# controller_board.net
KiCad netlist of a schematic drawn in EAGLE
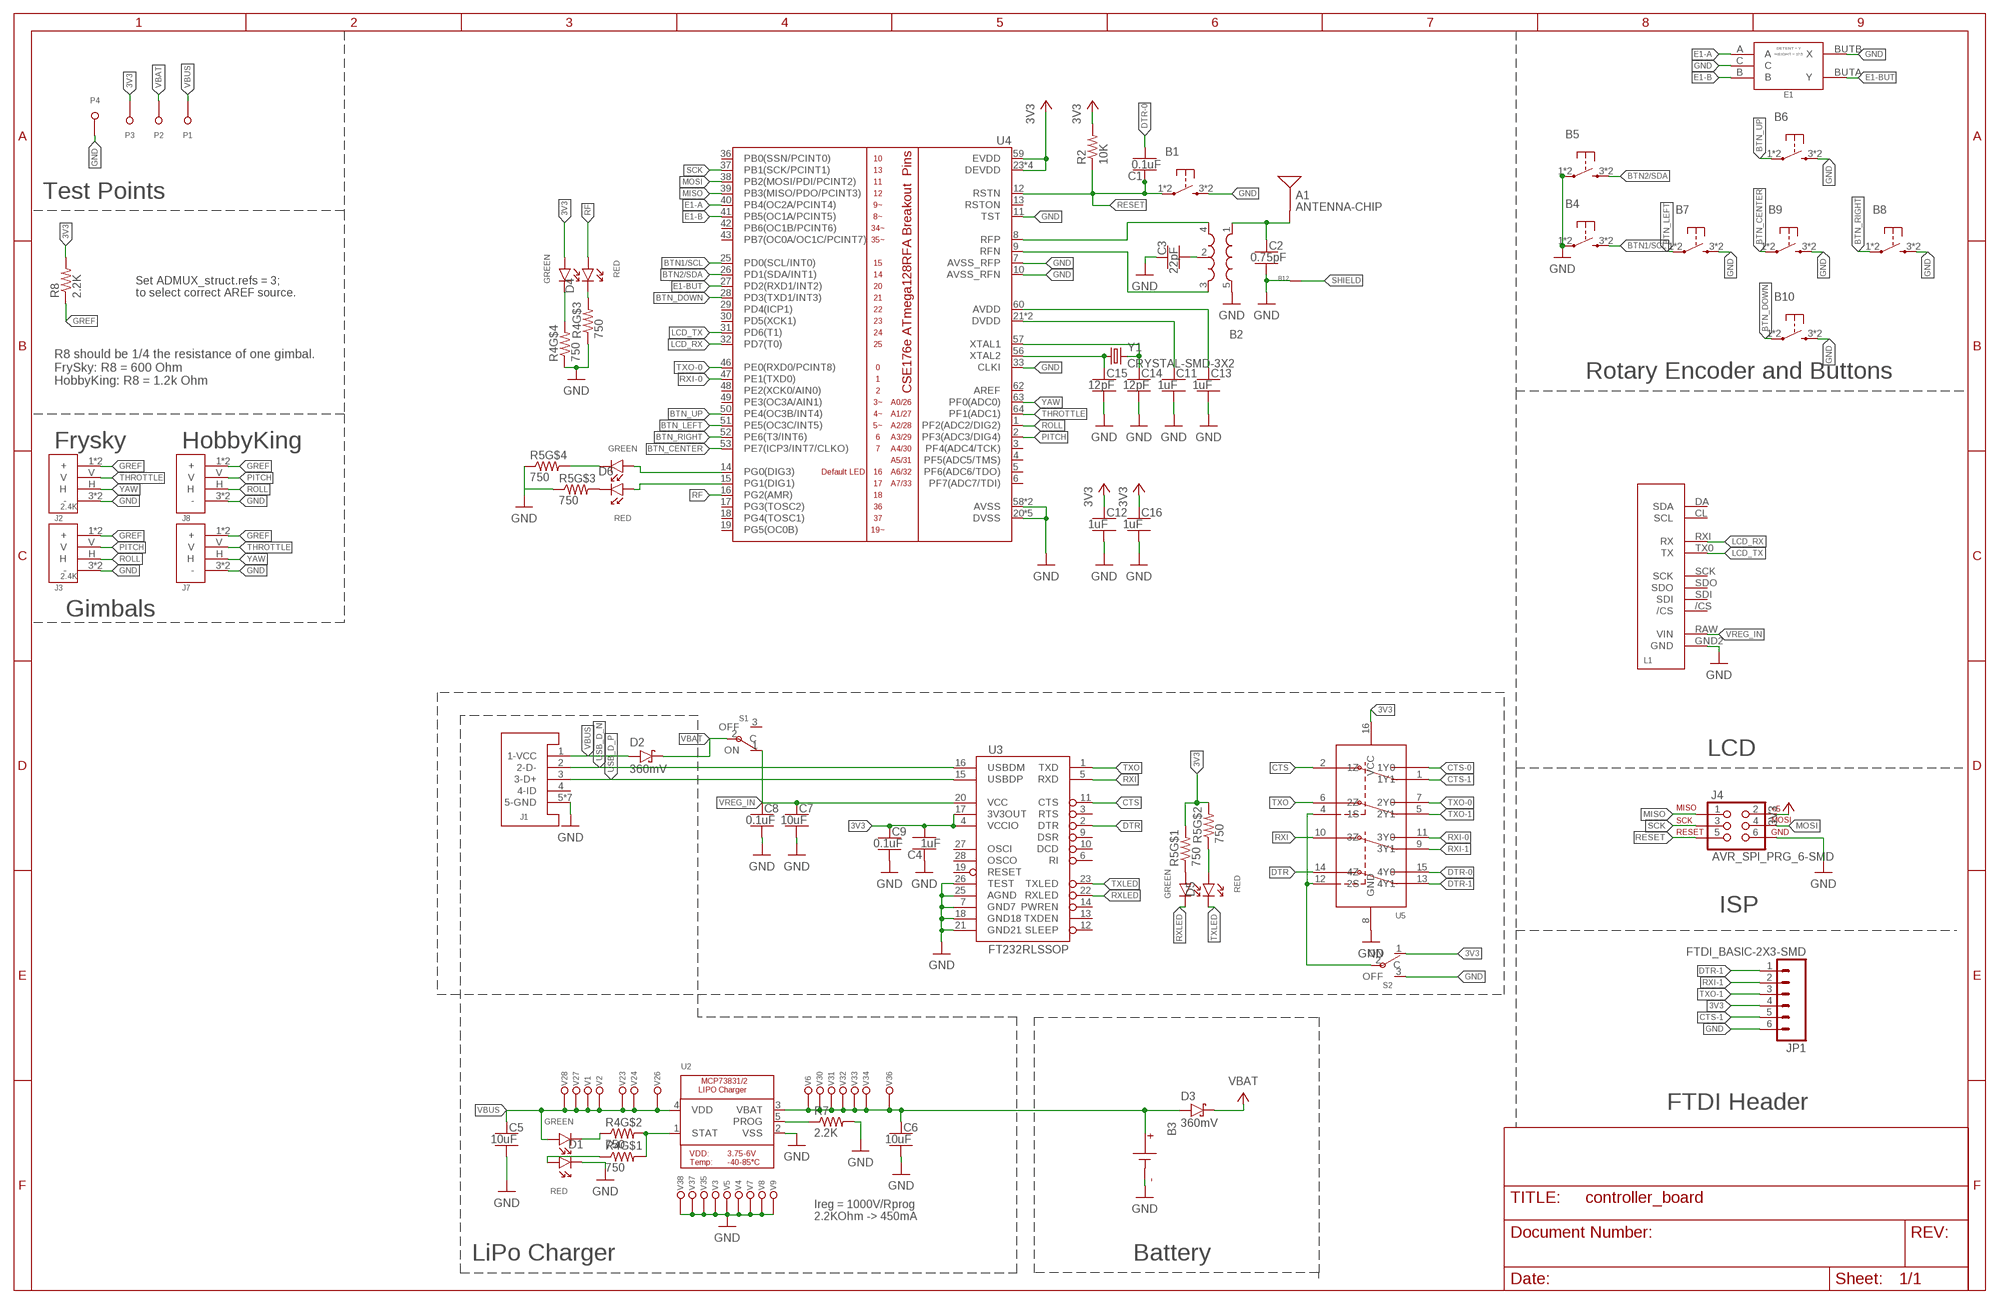
[diagram p0: schematic, sheet 1]

(export (version "E")
  (design (tool "Eeschema 10.0.6"))
  (components
    (comp (ref "A1")
      (value "ANTENNA-CHIP")
      (footprint "eagle-import:ANTENNA-CHIP")
      (fields
        (field (name "MFR") "Linx Technologies Inc.")
        (field (name "MPN") "ANT-2.45-CHP-T")
        (field (name "CREATOR") "Swanson")
        (field (name "REVIEWER") "Swanson")
      )
      (libsource (lib "eagle-import") (part "ANTENNA-CHIP"))
    )
    (comp (ref "B1")
      (value "PUSHBUTTON_-4.5X4.5")
      (footprint "eagle-import:4.5MM_TACTILE_SWITCH_TL3305AF160QG")
      (fields (field (name "CREATOR") "Swanson"))
      (libsource (lib "eagle-import") (part "PUSHBUTTON_-4.5X4.5"))
    )
    (comp (ref "B2")
      (value "BALUN0805")
      (footprint "eagle-import:BALUN")
      (fields
        (field (name "MFR") "Wurth Electronics Inc")
        (field (name "MPN") "748421245")
        (field (name "CREATOR") "Swanson")
        (field (name "REVIEWER") "Swanson")
      )
      (libsource (lib "eagle-import") (part "BALUN0805"))
    )
    (comp (ref "B3")
      (value "BATTERY-SMD")
      (footprint "eagle-import:MOLEX-BATTERY-CONNECTOR-SMD-51005-2P")
      (libsource (lib "eagle-import") (part "BATTERY-SMD"))
    )
    (comp (ref "B4")
      (value "PUSHBUTTON_-4.5X4.5")
      (footprint "eagle-import:4.5MM_TACTILE_SWITCH_TL3305AF160QG")
      (fields (field (name "CREATOR") "Swanson"))
      (libsource (lib "eagle-import") (part "PUSHBUTTON_-4.5X4.5"))
    )
    (comp (ref "B5")
      (value "PUSHBUTTON_-4.5X4.5")
      (footprint "eagle-import:4.5MM_TACTILE_SWITCH_TL3305AF160QG")
      (fields (field (name "CREATOR") "Swanson"))
      (libsource (lib "eagle-import") (part "PUSHBUTTON_-4.5X4.5"))
    )
    (comp (ref "B6")
      (value "PUSHBUTTON_-4.5X4.5")
      (footprint "eagle-import:4.5MM_TACTILE_SWITCH_TL3305AF160QG")
      (fields (field (name "CREATOR") "Swanson"))
      (libsource (lib "eagle-import") (part "PUSHBUTTON_-4.5X4.5"))
    )
    (comp (ref "B7")
      (value "PUSHBUTTON_-4.5X4.5")
      (footprint "eagle-import:4.5MM_TACTILE_SWITCH_TL3305AF160QG")
      (fields (field (name "CREATOR") "Swanson"))
      (libsource (lib "eagle-import") (part "PUSHBUTTON_-4.5X4.5"))
    )
    (comp (ref "B8")
      (value "PUSHBUTTON_-4.5X4.5")
      (footprint "eagle-import:4.5MM_TACTILE_SWITCH_TL3305AF160QG")
      (fields (field (name "CREATOR") "Swanson"))
      (libsource (lib "eagle-import") (part "PUSHBUTTON_-4.5X4.5"))
    )
    (comp (ref "B9")
      (value "PUSHBUTTON_-4.5X4.5")
      (footprint "eagle-import:4.5MM_TACTILE_SWITCH_TL3305AF160QG")
      (fields (field (name "CREATOR") "Swanson"))
      (libsource (lib "eagle-import") (part "PUSHBUTTON_-4.5X4.5"))
    )
    (comp (ref "B10")
      (value "PUSHBUTTON_-4.5X4.5")
      (footprint "eagle-import:4.5MM_TACTILE_SWITCH_TL3305AF160QG")
      (fields (field (name "CREATOR") "Swanson"))
      (libsource (lib "eagle-import") (part "PUSHBUTTON_-4.5X4.5"))
    )
    (comp (ref "B12")
      (value "NET_BRIDGE")
      (footprint "eagle-import:NET_BRIDGE")
      (fields (field (name "CREATOR") "Michael Gonzalez"))
      (libsource (lib "eagle-import") (part "NET_BRIDGE"))
    )
    (comp (ref "C1")
      (value "0.1uF")
      (footprint "eagle-import:CAPC1608X100")
      (fields (field (name "CREATOR") "Swanson"))
      (libsource (lib "eagle-import") (part "CAPACITOR-NP_SMD-0603_CERAMIC-0.1UF"))
    )
    (comp (ref "C2")
      (value "0.75pF")
      (footprint "eagle-import:CAPC1608X100")
      (fields (field (name "CREATOR") "Swanson"))
      (libsource (lib "eagle-import") (part "CAPACITOR-NP_SMD-0603_CERAMIC-0.75PF"))
    )
    (comp (ref "C3")
      (value "22pF")
      (footprint "eagle-import:CAPC1608X100")
      (fields (field (name "CREATOR") "Swanson"))
      (libsource (lib "eagle-import") (part "CAPACITOR-NP_SMD-0603_CERAMIC-22PF"))
    )
    (comp (ref "C4")
      (value "1uF")
      (footprint "eagle-import:CAPC1608X100")
      (fields (field (name "CREATOR") "Swanson"))
      (libsource (lib "eagle-import") (part "CAPACITOR-NP_SMD-0603_CERAMIC-1UF"))
    )
    (comp (ref "C5")
      (value "10uF")
      (footprint "eagle-import:CAPC1608X100")
      (fields (field (name "CREATOR") "Swanson"))
      (libsource (lib "eagle-import") (part "CAPACITOR-NP_SMD-0603_CERAMIC-10UF"))
    )
    (comp (ref "C6")
      (value "10uF")
      (footprint "eagle-import:CAPC1608X100")
      (fields (field (name "CREATOR") "Swanson"))
      (libsource (lib "eagle-import") (part "CAPACITOR-NP_SMD-0603_CERAMIC-10UF"))
    )
    (comp (ref "C7")
      (value "10uF")
      (footprint "eagle-import:CAPC1608X100")
      (fields (field (name "CREATOR") "Swanson"))
      (libsource (lib "eagle-import") (part "CAPACITOR-NP_SMD-0603_CERAMIC-10UF"))
    )
    (comp (ref "C8")
      (value "0.1uF")
      (footprint "eagle-import:CAPC1608X100")
      (fields (field (name "CREATOR") "Swanson"))
      (libsource (lib "eagle-import") (part "CAPACITOR-NP_SMD-0603_CERAMIC-0.1UF"))
    )
    (comp (ref "C9")
      (value "0.1uF")
      (footprint "eagle-import:CAPC1608X100")
      (fields (field (name "CREATOR") "Swanson"))
      (libsource (lib "eagle-import") (part "CAPACITOR-NP_SMD-0603_CERAMIC-0.1UF"))
    )
    (comp (ref "C11")
      (value "1uF")
      (footprint "eagle-import:CAPC1608X100")
      (fields (field (name "CREATOR") "Swanson"))
      (libsource (lib "eagle-import") (part "CAPACITOR-NP_SMD-0603_CERAMIC-1UF"))
    )
    (comp (ref "C12")
      (value "1uF")
      (footprint "eagle-import:CAPC1608X100")
      (fields (field (name "CREATOR") "Swanson"))
      (libsource (lib "eagle-import") (part "CAPACITOR-NP_SMD-0603_CERAMIC-1UF"))
    )
    (comp (ref "C13")
      (value "1uF")
      (footprint "eagle-import:CAPC1608X100")
      (fields (field (name "CREATOR") "Swanson"))
      (libsource (lib "eagle-import") (part "CAPACITOR-NP_SMD-0603_CERAMIC-1UF"))
    )
    (comp (ref "C14")
      (value "12pF")
      (footprint "eagle-import:CAPC1608X100")
      (fields (field (name "CREATOR") "Swanson"))
      (libsource (lib "eagle-import") (part "CAPACITOR-NP_SMD-0603_CERAMIC-12PF"))
    )
    (comp (ref "C15")
      (value "12pF")
      (footprint "eagle-import:CAPC1608X100")
      (fields (field (name "CREATOR") "Swanson"))
      (libsource (lib "eagle-import") (part "CAPACITOR-NP_SMD-0603_CERAMIC-12PF"))
    )
    (comp (ref "C16")
      (value "1uF")
      (footprint "eagle-import:CAPC1608X100")
      (fields (field (name "CREATOR") "Swanson"))
      (libsource (lib "eagle-import") (part "CAPACITOR-NP_SMD-0603_CERAMIC-1UF"))
    )
    (comp (ref "D1")
      (value "LED-2X-GREEN/RED-1.6X1.5MM")
      (footprint "eagle-import:LED-2X-LITE-ON-1.6MMX1.5MM")
      (fields
        (field (name "COLOR2") "RED")
        (field (name "COLOR1") "GREEN")
        (field (name "CREATOR") "Swanson")
      )
      (libsource (lib "eagle-import") (part "LED-2X-GREEN/RED-1.6X1.5MM"))
    )
    (comp (ref "D2")
      (value "360mV")
      (footprint "eagle-import:SOD3716X135_HS")
      (fields
        (field (name "MFR") "Toshiba Semiconductor and Storage")
        (field (name "MPN") "CRS08(TE85L,Q,M)")
        (field (name "CREATOR") "Swanson")
        (field (name "REVIEWER") "Swanson")
      )
      (libsource (lib "eagle-import") (part "DIODE-SCHOTTKY_SMD-SOD123-360MV"))
    )
    (comp (ref "D3")
      (value "360mV")
      (footprint "eagle-import:SOD3716X135_HS")
      (fields
        (field (name "MFR") "Toshiba Semiconductor and Storage")
        (field (name "MPN") "CRS08(TE85L,Q,M)")
        (field (name "CREATOR") "Swanson")
        (field (name "REVIEWER") "Swanson")
      )
      (libsource (lib "eagle-import") (part "DIODE-SCHOTTKY_SMD-SOD123-360MV"))
    )
    (comp (ref "D4")
      (value "LED-2X-GREEN/RED-1.6X1.5MM")
      (footprint "eagle-import:LED-2X-LITE-ON-1.6MMX1.5MM")
      (fields
        (field (name "COLOR2") "RED")
        (field (name "COLOR1") "GREEN")
        (field (name "CREATOR") "Swanson")
      )
      (libsource (lib "eagle-import") (part "LED-2X-GREEN/RED-1.6X1.5MM"))
    )
    (comp (ref "D5")
      (value "LED-2X-GREEN/RED-1.6X1.5MM")
      (footprint "eagle-import:LED-2X-LITE-ON-1.6MMX1.5MM")
      (fields
        (field (name "COLOR2") "RED")
        (field (name "COLOR1") "GREEN")
        (field (name "CREATOR") "Swanson")
      )
      (libsource (lib "eagle-import") (part "LED-2X-GREEN/RED-1.6X1.5MM"))
    )
    (comp (ref "D6")
      (value "LED-2X-GREEN/RED-1.6X1.5MM")
      (footprint "eagle-import:LED-2X-LITE-ON-1.6MMX1.5MM")
      (fields
        (field (name "COLOR2") "RED")
        (field (name "COLOR1") "GREEN")
        (field (name "CREATOR") "Swanson")
      )
      (libsource (lib "eagle-import") (part "LED-2X-GREEN/RED-1.6X1.5MM"))
    )
    (comp (ref "E1")
      (value "ROTARY-ENCODER-W/BUTTON-BOURNS-PEC12R-4217F")
      (footprint "eagle-import:BOURNS-PEC12R")
      (fields (field (name "DETENT") "Y") (field (name "HEIGHT") "17.5") (field (name "CREATOR") "Swanson"))
      (libsource (lib "eagle-import") (part "ROTARY-ENCODER-W/BUTTON-BOURNS-PEC12R-4217F"))
    )
    (comp (ref "J1")
      (value "USB-MICROA-AMPHENOL-10118192-0001LF")
      (footprint "eagle-import:USB-MICROA-10118192-0001LF")
      (fields (field (name "CREATOR") "Swanson"))
      (libsource (lib "eagle-import") (part "USB-MICROA-AMPHENOL-10118192-0001LF"))
    )
    (comp (ref "J2")
      (value "2.4K")
      (footprint "eagle-import:JST-13-PTH")
      (fields (field (name "CREATOR") "Swanson"))
      (libsource (lib "eagle-import") (part "FRSKY-GIMBAL-FRYSKY"))
    )
    (comp (ref "J3")
      (value "2.4K")
      (footprint "eagle-import:JST-13-PTH")
      (fields (field (name "SPICEPREFIX") "E") (field (name "CREATOR") "Swanson"))
      (libsource (lib "eagle-import") (part "FRSKY-GIMBAL-FRYSKY"))
    )
    (comp (ref "J4")
      (value "AVR_SPI_PRG_6-SMD")
      (footprint "eagle-import:2X3-SMD")
      (fields (field (name "CREATOR") "Swanson"))
      (libsource (lib "eagle-import") (part "AVR_SPI_PRG_6-SMD"))
    )
    (comp (ref "J7")
      (value "FRSKY-GIMBAL-2X-SERVO-SMD")
      (footprint "eagle-import:2X-SERVO-SMD")
      (libsource (lib "eagle-import") (part "FRSKY-GIMBAL-2X-SERVO-SMD"))
    )
    (comp (ref "J8")
      (value "FRSKY-GIMBAL-2X-SERVO-SMD")
      (footprint "eagle-import:2X-SERVO-SMD")
      (libsource (lib "eagle-import") (part "FRSKY-GIMBAL-2X-SERVO-SMD"))
    )
    (comp (ref "JP1")
      (value "FTDI_BASIC-2X3-SMD")
      (footprint "eagle-import:FTDI-2X3-SMD")
      (fields (field (name "CREATOR") "Swanson"))
      (libsource (lib "eagle-import") (part "FTDI_BASIC-2X3-SMD"))
    )
    (comp (ref "L1")
      (value "SPARKFUN_SERLCD_SERIAL_REDUCED-SMD")
      (footprint "eagle-import:SPARKFUN_SERLCD_16X2_REDUCED_SMD")
      (fields (field (name "CREATOR") "Swanson"))
      (libsource (lib "eagle-import") (part "SPARKFUN_SERLCD_SERIAL_REDUCED-SMD"))
    )
    (comp (ref "P1")
      (value "TEST-POINT")
      (footprint "eagle-import:TEST-POINT-KEYSTONE-5000")
      (fields (field (name "CREATOR") "Swanson"))
      (libsource (lib "eagle-import") (part "TEST-POINT"))
    )
    (comp (ref "P2")
      (value "TEST-POINT")
      (footprint "eagle-import:TEST-POINT-KEYSTONE-5000")
      (fields (field (name "CREATOR") "Swanson"))
      (libsource (lib "eagle-import") (part "TEST-POINT"))
    )
    (comp (ref "P3")
      (value "TEST-POINT")
      (footprint "eagle-import:TEST-POINT-KEYSTONE-5000")
      (fields (field (name "CREATOR") "Swanson"))
      (libsource (lib "eagle-import") (part "TEST-POINT"))
    )
    (comp (ref "P4")
      (value "TEST-POINT")
      (footprint "eagle-import:TEST-POINT-KEYSTONE-5000")
      (fields (field (name "CREATOR") "Swanson"))
      (libsource (lib "eagle-import") (part "TEST-POINT"))
    )
    (comp (ref "R2")
      (value "10K")
      (footprint "eagle-import:RESC1608X55")
      (fields (field (name "CREATOR") "Swanson"))
      (libsource (lib "eagle-import") (part "RESISTOR_SMD-0603-10K"))
    )
    (comp (ref "R4")
      (value "750")
      (footprint "eagle-import:RESCAXS50P200X100X45-8")
      (fields (field (name "CREATOR") "Swanson"))
      (libsource (lib "eagle-import") (part "RESISTOR-PACK-4X-750"))
    )
    (comp (ref "R5")
      (value "750")
      (footprint "eagle-import:RESCAXS50P200X100X45-8")
      (fields (field (name "CREATOR") "Swanson"))
      (libsource (lib "eagle-import") (part "RESISTOR-PACK-4X-750"))
    )
    (comp (ref "R7")
      (value "2.2K")
      (footprint "eagle-import:RESC1608X55")
      (fields (field (name "CREATOR") "Swanson"))
      (libsource (lib "eagle-import") (part "RESISTOR_SMD-0603-2.2K"))
    )
    (comp (ref "R8")
      (value "2.2K")
      (footprint "eagle-import:RESC1608X55")
      (fields (field (name "CREATOR") "Swanson"))
      (libsource (lib "eagle-import") (part "RESISTOR_SMD-0603-2.2K"))
    )
    (comp (ref "S1")
      (value "POWER-SWITCH-MFS201N-9-Z-SMD-VERTICAL")
      (footprint "eagle-import:JS102011JCQN")
      (fields (field (name "CREATOR") "Swanson"))
      (libsource (lib "eagle-import") (part "POWER-SWITCH-MFS201N-9-Z-SMD-VERTICAL"))
    )
    (comp (ref "S2")
      (value "POWER-SWITCH-MFS201N-9-Z-SMD-VERTICAL")
      (footprint "eagle-import:JS102011JCQN")
      (fields (field (name "CREATOR") "Swanson"))
      (libsource (lib "eagle-import") (part "POWER-SWITCH-MFS201N-9-Z-SMD-VERTICAL"))
    )
    (comp (ref "U2")
      (value "MCP73831T-2ACI/OT")
      (footprint "eagle-import:SOT23-5")
      (fields (field (name "CREATOR") "Adafruit"))
      (libsource (lib "eagle-import") (part "MCP73831/2"))
    )
    (comp (ref "U3")
      (value "FT232RLSSOP")
      (footprint "eagle-import:SSOP28DB")
      (fields (field (name "CREATOR") "Swanson"))
      (libsource (lib "eagle-import") (part "FT232RLSSOP"))
    )
    (comp (ref "U4")
      (value "ATMEGA128RFA1")
      (footprint "eagle-import:QFN-64")
      (fields
        (field (name "MFR") "Atmel")
        (field (name "MPN") "ATMEGA128RFA1-ZUR00")
        (field (name "CREATOR") "Swanson")
        (field (name "REVIEWER") "Swanson")
      )
      (libsource (lib "eagle-import") (part "ATMEGA128RFA1"))
    )
    (comp (ref "U5")
      (value "DPDT-X2")
      (footprint "eagle-import:SOP65P640X110-16")
      (fields (field (name "CREATOR") "Swanson"))
      (libsource (lib "eagle-import") (part "DPDT-X2"))
    )
    (comp (ref "V1")
      (value "LOCKED-VIA-0.2")
      (footprint "eagle-import:VIA-0.2MM")
      (fields (field (name "CREATOR") "Swanson"))
      (libsource (lib "eagle-import") (part "LOCKED-VIA-0.2"))
    )
    (comp (ref "V2")
      (value "LOCKED-VIA-0.2")
      (footprint "eagle-import:VIA-0.2MM")
      (fields (field (name "CREATOR") "Swanson"))
      (libsource (lib "eagle-import") (part "LOCKED-VIA-0.2"))
    )
    (comp (ref "V3")
      (value "LOCKED-VIA-0.2")
      (footprint "eagle-import:VIA-0.2MM")
      (fields (field (name "CREATOR") "Swanson"))
      (libsource (lib "eagle-import") (part "LOCKED-VIA-0.2"))
    )
    (comp (ref "V4")
      (value "LOCKED-VIA-0.2")
      (footprint "eagle-import:VIA-0.2MM")
      (fields (field (name "CREATOR") "Swanson"))
      (libsource (lib "eagle-import") (part "LOCKED-VIA-0.2"))
    )
    (comp (ref "V5")
      (value "LOCKED-VIA-0.2")
      (footprint "eagle-import:VIA-0.2MM")
      (fields (field (name "CREATOR") "Swanson"))
      (libsource (lib "eagle-import") (part "LOCKED-VIA-0.2"))
    )
    (comp (ref "V6")
      (value "LOCKED-VIA-0.2")
      (footprint "eagle-import:VIA-0.2MM")
      (fields (field (name "CREATOR") "Swanson"))
      (libsource (lib "eagle-import") (part "LOCKED-VIA-0.2"))
    )
    (comp (ref "V7")
      (value "LOCKED-VIA-0.2")
      (footprint "eagle-import:VIA-0.2MM")
      (fields (field (name "CREATOR") "Swanson"))
      (libsource (lib "eagle-import") (part "LOCKED-VIA-0.2"))
    )
    (comp (ref "V8")
      (value "LOCKED-VIA-0.2")
      (footprint "eagle-import:VIA-0.2MM")
      (fields (field (name "CREATOR") "Swanson"))
      (libsource (lib "eagle-import") (part "LOCKED-VIA-0.2"))
    )
    (comp (ref "V9")
      (value "LOCKED-VIA-0.2")
      (footprint "eagle-import:VIA-0.2MM")
      (fields (field (name "CREATOR") "Swanson"))
      (libsource (lib "eagle-import") (part "LOCKED-VIA-0.2"))
    )
    (comp (ref "V23")
      (value "LOCKED-VIA-0.2")
      (footprint "eagle-import:VIA-0.2MM")
      (fields (field (name "CREATOR") "Swanson"))
      (libsource (lib "eagle-import") (part "LOCKED-VIA-0.2"))
    )
    (comp (ref "V24")
      (value "LOCKED-VIA-0.2")
      (footprint "eagle-import:VIA-0.2MM")
      (fields (field (name "CREATOR") "Swanson"))
      (libsource (lib "eagle-import") (part "LOCKED-VIA-0.2"))
    )
    (comp (ref "V26")
      (value "LOCKED-VIA-0.2")
      (footprint "eagle-import:VIA-0.2MM")
      (fields (field (name "CREATOR") "Swanson"))
      (libsource (lib "eagle-import") (part "LOCKED-VIA-0.2"))
    )
    (comp (ref "V27")
      (value "LOCKED-VIA-0.2")
      (footprint "eagle-import:VIA-0.2MM")
      (fields (field (name "CREATOR") "Swanson"))
      (libsource (lib "eagle-import") (part "LOCKED-VIA-0.2"))
    )
    (comp (ref "V28")
      (value "LOCKED-VIA-0.2")
      (footprint "eagle-import:VIA-0.2MM")
      (fields (field (name "CREATOR") "Swanson"))
      (libsource (lib "eagle-import") (part "LOCKED-VIA-0.2"))
    )
    (comp (ref "V30")
      (value "LOCKED-VIA-0.2")
      (footprint "eagle-import:VIA-0.2MM")
      (fields (field (name "CREATOR") "Swanson"))
      (libsource (lib "eagle-import") (part "LOCKED-VIA-0.2"))
    )
    (comp (ref "V31")
      (value "LOCKED-VIA-0.2")
      (footprint "eagle-import:VIA-0.2MM")
      (fields (field (name "CREATOR") "Swanson"))
      (libsource (lib "eagle-import") (part "LOCKED-VIA-0.2"))
    )
    (comp (ref "V32")
      (value "LOCKED-VIA-0.2")
      (footprint "eagle-import:VIA-0.2MM")
      (fields (field (name "CREATOR") "Swanson"))
      (libsource (lib "eagle-import") (part "LOCKED-VIA-0.2"))
    )
    (comp (ref "V33")
      (value "LOCKED-VIA-0.2")
      (footprint "eagle-import:VIA-0.2MM")
      (fields (field (name "CREATOR") "Swanson"))
      (libsource (lib "eagle-import") (part "LOCKED-VIA-0.2"))
    )
    (comp (ref "V34")
      (value "LOCKED-VIA-0.2")
      (footprint "eagle-import:VIA-0.2MM")
      (fields (field (name "CREATOR") "Swanson"))
      (libsource (lib "eagle-import") (part "LOCKED-VIA-0.2"))
    )
    (comp (ref "V35")
      (value "LOCKED-VIA-0.2")
      (footprint "eagle-import:VIA-0.2MM")
      (fields (field (name "CREATOR") "Swanson"))
      (libsource (lib "eagle-import") (part "LOCKED-VIA-0.2"))
    )
    (comp (ref "V36")
      (value "LOCKED-VIA-0.2")
      (footprint "eagle-import:VIA-0.2MM")
      (fields (field (name "CREATOR") "Swanson"))
      (libsource (lib "eagle-import") (part "LOCKED-VIA-0.2"))
    )
    (comp (ref "V37")
      (value "LOCKED-VIA-0.2")
      (footprint "eagle-import:VIA-0.2MM")
      (fields (field (name "CREATOR") "Swanson"))
      (libsource (lib "eagle-import") (part "LOCKED-VIA-0.2"))
    )
    (comp (ref "V38")
      (value "LOCKED-VIA-0.2")
      (footprint "eagle-import:VIA-0.2MM")
      (fields (field (name "CREATOR") "Swanson"))
      (libsource (lib "eagle-import") (part "LOCKED-VIA-0.2"))
    )
    (comp (ref "Y1")
      (value "CRYSTAL-SMD-3X2")
      (footprint "eagle-import:OSCCC320X250X85")
      (fields (field (name "CREATOR") "Swanson"))
      (libsource (lib "eagle-import") (part "CRYSTAL-SMD-3X2"))
    )
  )
  (nets
    (net (code "1") (name "3V3") (class "Default")
      (node (ref "C12") (pin "1") (pinfunction "1_1") (pintype "passive"))
      (node (ref "C16") (pin "1") (pinfunction "1_1") (pintype "passive"))
      (node (ref "C4") (pin "2") (pinfunction "2_2") (pintype "passive"))
      (node (ref "C9") (pin "1") (pinfunction "1_1") (pintype "passive"))
      (node (ref "D4") (pin "A2") (pinfunction "A2_A2") (pintype "passive"))
      (node (ref "J4") (pin "2") (pinfunction "2_2") (pintype "passive"))
      (node (ref "JP1") (pin "4") (pinfunction "4_4") (pintype "passive"))
      (node (ref "P3") (pin "T") (pinfunction "T_T") (pintype "bidirectional"))
      (node (ref "R2") (pin "2") (pinfunction "2_2") (pintype "passive"))
      (node (ref "R5") (pin "5") (pinfunction "2_5") (pintype "passive"))
      (node (ref "R5") (pin "6") (pinfunction "2_6") (pintype "passive"))
      (node (ref "R8") (pin "2") (pinfunction "2_2") (pintype "passive"))
      (node (ref "S2") (pin "1") (pinfunction "ON_1") (pintype "bidirectional"))
      (node (ref "U3") (pin "17") (pinfunction "3V3OUT_17") (pintype "output"))
      (node (ref "U3") (pin "4") (pinfunction "VCCIO_4") (pintype "power_in"))
      (node (ref "U4") (pin "23") (pinfunction "DEVDD_23") (pintype "bidirectional"))
      (node (ref "U4") (pin "34") (pinfunction "DEVDD_34") (pintype "bidirectional"))
      (node (ref "U4") (pin "44") (pinfunction "DEVDD_44") (pintype "bidirectional"))
      (node (ref "U4") (pin "54") (pinfunction "DEVDD_54") (pintype "bidirectional"))
      (node (ref "U4") (pin "59") (pinfunction "EVDD_59") (pintype "bidirectional"))
      (node (ref "U5") (pin "16") (pinfunction "VCC_16") (pintype "bidirectional"))
    )
    (net (code "2") (name "BTN1{slash}SCL") (class "Default")
      (node (ref "B4") (pin "3") (pinfunction "2_3") (pintype "passive"))
      (node (ref "B4") (pin "4") (pinfunction "2_4") (pintype "passive"))
      (node (ref "U4") (pin "25") (pinfunction "PD0(SCL/INT0)_25") (pintype "bidirectional"))
    )
    (net (code "3") (name "BTN2{slash}SDA") (class "Default")
      (node (ref "B5") (pin "3") (pinfunction "2_3") (pintype "passive"))
      (node (ref "B5") (pin "4") (pinfunction "2_4") (pintype "passive"))
      (node (ref "U4") (pin "26") (pinfunction "PD1(SDA/INT1)_26") (pintype "bidirectional"))
    )
    (net (code "4") (name "BTN_CENTER") (class "Default")
      (node (ref "B9") (pin "1") (pinfunction "1_1") (pintype "passive"))
      (node (ref "B9") (pin "2") (pinfunction "1_2") (pintype "passive"))
      (node (ref "U4") (pin "53") (pinfunction "PE7(ICP3/INT7/CLKO)_53") (pintype "bidirectional"))
    )
    (net (code "5") (name "BTN_DOWN") (class "Default")
      (node (ref "B10") (pin "1") (pinfunction "1_1") (pintype "passive"))
      (node (ref "B10") (pin "2") (pinfunction "1_2") (pintype "passive"))
      (node (ref "U4") (pin "28") (pinfunction "PD3(TXD1/INT3)_28") (pintype "bidirectional"))
    )
    (net (code "6") (name "BTN_LEFT") (class "Default")
      (node (ref "B7") (pin "1") (pinfunction "1_1") (pintype "passive"))
      (node (ref "B7") (pin "2") (pinfunction "1_2") (pintype "passive"))
      (node (ref "U4") (pin "51") (pinfunction "PE5(OC3C/INT5)_51") (pintype "bidirectional"))
    )
    (net (code "7") (name "BTN_RIGHT") (class "Default")
      (node (ref "B8") (pin "1") (pinfunction "1_1") (pintype "passive"))
      (node (ref "B8") (pin "2") (pinfunction "1_2") (pintype "passive"))
      (node (ref "U4") (pin "52") (pinfunction "PE6(T3/INT6)_52") (pintype "bidirectional"))
    )
    (net (code "8") (name "BTN_UP") (class "Default")
      (node (ref "B6") (pin "1") (pinfunction "1_1") (pintype "passive"))
      (node (ref "B6") (pin "2") (pinfunction "1_2") (pintype "passive"))
      (node (ref "U4") (pin "50") (pinfunction "PE4(OC3B/INT4)_50") (pintype "bidirectional"))
    )
    (net (code "9") (name "CTS") (class "Default")
      (node (ref "U3") (pin "11") (pinfunction "CTS_11") (pintype "input"))
      (node (ref "U5") (pin "2") (pinfunction "1Z_2") (pintype "bidirectional"))
    )
    (net (code "10") (name "CTS-0") (class "Default")
      (node (ref "U5") (pin "3") (pinfunction "1Y0_3") (pintype "bidirectional"))
    )
    (net (code "11") (name "CTS-1") (class "Default")
      (node (ref "JP1") (pin "5") (pinfunction "5_5") (pintype "passive"))
      (node (ref "U5") (pin "1") (pinfunction "1Y1_1") (pintype "bidirectional"))
    )
    (net (code "12") (name "DTR") (class "Default")
      (node (ref "U3") (pin "2") (pinfunction "DTR_2") (pintype "output"))
      (node (ref "U5") (pin "14") (pinfunction "4Z_14") (pintype "bidirectional"))
    )
    (net (code "13") (name "DTR-0") (class "Default")
      (node (ref "C1") (pin "2") (pinfunction "2_2") (pintype "passive"))
      (node (ref "U5") (pin "15") (pinfunction "4Y0_15") (pintype "bidirectional"))
    )
    (net (code "14") (name "DTR-1") (class "Default")
      (node (ref "JP1") (pin "1") (pinfunction "1_1") (pintype "passive"))
      (node (ref "U5") (pin "13") (pinfunction "4Y1_13") (pintype "bidirectional"))
    )
    (net (code "15") (name "E1-A") (class "Default")
      (node (ref "E1") (pin "A") (pinfunction "A_A") (pintype "bidirectional"))
      (node (ref "U4") (pin "40") (pinfunction "PB4(OC2A/PCINT4)_40") (pintype "bidirectional"))
    )
    (net (code "16") (name "E1-B") (class "Default")
      (node (ref "E1") (pin "B") (pinfunction "B_B") (pintype "bidirectional"))
      (node (ref "U4") (pin "41") (pinfunction "PB5(OC1A/PCINT5)_41") (pintype "bidirectional"))
    )
    (net (code "17") (name "E1-BUT") (class "Default")
      (node (ref "E1") (pin "BUTA") (pinfunction "Y_BUTA") (pintype "bidirectional"))
      (node (ref "U4") (pin "27") (pinfunction "PD2(RXD1/INT2)_27") (pintype "bidirectional"))
    )
    (net (code "18") (name "GND") (class "Default")
      (node (ref "B1") (pin "3") (pinfunction "2_3") (pintype "passive"))
      (node (ref "B1") (pin "4") (pinfunction "2_4") (pintype "passive"))
      (node (ref "B10") (pin "3") (pinfunction "2_3") (pintype "passive"))
      (node (ref "B10") (pin "4") (pinfunction "2_4") (pintype "passive"))
      (node (ref "B12") (pin "P1") (pinfunction "P1_P1") (pintype "bidirectional"))
      (node (ref "B2") (pin "5") (pinfunction "GND_5") (pintype "bidirectional"))
      (node (ref "B3") (pin "G") (pinfunction "N_G") (pintype "bidirectional"))
      (node (ref "B3") (pin "G2") (pinfunction "N_G2") (pintype "bidirectional"))
      (node (ref "B3") (pin "G3") (pinfunction "N_G3") (pintype "bidirectional"))
      (node (ref "B4") (pin "1") (pinfunction "1_1") (pintype "passive"))
      (node (ref "B4") (pin "2") (pinfunction "1_2") (pintype "passive"))
      (node (ref "B5") (pin "1") (pinfunction "1_1") (pintype "passive"))
      (node (ref "B5") (pin "2") (pinfunction "1_2") (pintype "passive"))
      (node (ref "B6") (pin "3") (pinfunction "2_3") (pintype "passive"))
      (node (ref "B6") (pin "4") (pinfunction "2_4") (pintype "passive"))
      (node (ref "B7") (pin "3") (pinfunction "2_3") (pintype "passive"))
      (node (ref "B7") (pin "4") (pinfunction "2_4") (pintype "passive"))
      (node (ref "B8") (pin "3") (pinfunction "2_3") (pintype "passive"))
      (node (ref "B8") (pin "4") (pinfunction "2_4") (pintype "passive"))
      (node (ref "B9") (pin "3") (pinfunction "2_3") (pintype "passive"))
      (node (ref "B9") (pin "4") (pinfunction "2_4") (pintype "passive"))
      (node (ref "C11") (pin "2") (pinfunction "2_2") (pintype "passive"))
      (node (ref "C12") (pin "2") (pinfunction "2_2") (pintype "passive"))
      (node (ref "C13") (pin "2") (pinfunction "2_2") (pintype "passive"))
      (node (ref "C14") (pin "2") (pinfunction "2_2") (pintype "passive"))
      (node (ref "C15") (pin "2") (pinfunction "2_2") (pintype "passive"))
      (node (ref "C16") (pin "2") (pinfunction "2_2") (pintype "passive"))
      (node (ref "C2") (pin "2") (pinfunction "2_2") (pintype "passive"))
      (node (ref "C3") (pin "1") (pinfunction "1_1") (pintype "passive"))
      (node (ref "C4") (pin "1") (pinfunction "1_1") (pintype "passive"))
      (node (ref "C5") (pin "2") (pinfunction "2_2") (pintype "passive"))
      (node (ref "C6") (pin "2") (pinfunction "2_2") (pintype "passive"))
      (node (ref "C7") (pin "2") (pinfunction "2_2") (pintype "passive"))
      (node (ref "C8") (pin "2") (pinfunction "2_2") (pintype "passive"))
      (node (ref "C9") (pin "2") (pinfunction "2_2") (pintype "passive"))
      (node (ref "D1") (pin "C1") (pinfunction "C1_C1") (pintype "passive"))
      (node (ref "E1") (pin "BUTB") (pinfunction "X_BUTB") (pintype "bidirectional"))
      (node (ref "E1") (pin "C") (pinfunction "C_C") (pintype "bidirectional"))
      (node (ref "J1") (pin "10") (pinfunction "5-GND_10") (pintype "bidirectional"))
      (node (ref "J1") (pin "11") (pinfunction "5-GND_11") (pintype "bidirectional"))
      (node (ref "J1") (pin "5") (pinfunction "5-GND_5") (pintype "bidirectional"))
      (node (ref "J1") (pin "6") (pinfunction "5-GND_6") (pintype "bidirectional"))
      (node (ref "J1") (pin "7") (pinfunction "5-GND_7") (pintype "bidirectional"))
      (node (ref "J1") (pin "8") (pinfunction "5-GND_8") (pintype "bidirectional"))
      (node (ref "J1") (pin "9") (pinfunction "5-GND_9") (pintype "bidirectional"))
      (node (ref "J2") (pin "3") (pinfunction "-_3") (pintype "bidirectional"))
      (node (ref "J2") (pin "6") (pinfunction "-_6") (pintype "bidirectional"))
      (node (ref "J3") (pin "3") (pinfunction "-_3") (pintype "bidirectional"))
      (node (ref "J3") (pin "6") (pinfunction "-_6") (pintype "bidirectional"))
      (node (ref "J4") (pin "6") (pinfunction "6_6") (pintype "passive"))
      (node (ref "J7") (pin "3") (pinfunction "-_3") (pintype "bidirectional"))
      (node (ref "J7") (pin "6") (pinfunction "-_6") (pintype "bidirectional"))
      (node (ref "J8") (pin "3") (pinfunction "-_3") (pintype "bidirectional"))
      (node (ref "J8") (pin "6") (pinfunction "-_6") (pintype "bidirectional"))
      (node (ref "JP1") (pin "6") (pinfunction "6_6") (pintype "passive"))
      (node (ref "L1") (pin "GND2") (pinfunction "GND_GND2") (pintype "bidirectional"))
      (node (ref "P4") (pin "T") (pinfunction "T_T") (pintype "bidirectional"))
      (node (ref "R4") (pin "1") (pinfunction "1_1") (pintype "passive"))
      (node (ref "R4") (pin "2") (pinfunction "1_2") (pintype "passive"))
      (node (ref "R5") (pin "1") (pinfunction "1_1") (pintype "passive"))
      (node (ref "R5") (pin "2") (pinfunction "1_2") (pintype "passive"))
      (node (ref "R7") (pin "2") (pinfunction "2_2") (pintype "passive"))
      (node (ref "S2") (pin "3") (pinfunction "OFF_3") (pintype "bidirectional"))
      (node (ref "U2") (pin "2") (pinfunction "VSS_2") (pintype "power_in"))
      (node (ref "U3") (pin "18") (pinfunction "GND18_18") (pintype "power_in"))
      (node (ref "U3") (pin "21") (pinfunction "GND21_21") (pintype "power_in"))
      (node (ref "U3") (pin "25") (pinfunction "AGND_25") (pintype "power_in"))
      (node (ref "U3") (pin "26") (pinfunction "TEST_26") (pintype "input"))
      (node (ref "U3") (pin "7") (pinfunction "GND7_7") (pintype "power_in"))
      (node (ref "U4") (pin "10") (pinfunction "AVSS_RFN_10") (pintype "bidirectional"))
      (node (ref "U4") (pin "11") (pinfunction "TST_11") (pintype "bidirectional"))
      (node (ref "U4") (pin "20") (pinfunction "DVSS_20") (pintype "bidirectional"))
      (node (ref "U4") (pin "24") (pinfunction "DVSS_24") (pintype "bidirectional"))
      (node (ref "U4") (pin "33") (pinfunction "CLKI_33") (pintype "bidirectional"))
      (node (ref "U4") (pin "35") (pinfunction "DVSS_35") (pintype "bidirectional"))
      (node (ref "U4") (pin "45") (pinfunction "DVSS_45") (pintype "bidirectional"))
      (node (ref "U4") (pin "55") (pinfunction "DVSS_55") (pintype "bidirectional"))
      (node (ref "U4") (pin "58") (pinfunction "AVSS_58") (pintype "bidirectional"))
      (node (ref "U4") (pin "61") (pinfunction "AVSS_61") (pintype "bidirectional"))
      (node (ref "U4") (pin "7") (pinfunction "AVSS_RFP_7") (pintype "bidirectional"))
      (node (ref "U5") (pin "8") (pinfunction "GND_8") (pintype "bidirectional"))
      (node (ref "V3") (pin "P1") (pinfunction "N_P1") (pintype "bidirectional"))
      (node (ref "V35") (pin "P1") (pinfunction "N_P1") (pintype "bidirectional"))
      (node (ref "V37") (pin "P1") (pinfunction "N_P1") (pintype "bidirectional"))
      (node (ref "V38") (pin "P1") (pinfunction "N_P1") (pintype "bidirectional"))
      (node (ref "V4") (pin "P1") (pinfunction "N_P1") (pintype "bidirectional"))
      (node (ref "V5") (pin "P1") (pinfunction "N_P1") (pintype "bidirectional"))
      (node (ref "V7") (pin "P1") (pinfunction "N_P1") (pintype "bidirectional"))
      (node (ref "V8") (pin "P1") (pinfunction "N_P1") (pintype "bidirectional"))
      (node (ref "V9") (pin "P1") (pinfunction "N_P1") (pintype "bidirectional"))
    )
    (net (code "19") (name "GREF") (class "Default")
      (node (ref "J2") (pin "1") (pinfunction "+_1") (pintype "bidirectional"))
      (node (ref "J2") (pin "4") (pinfunction "+_4") (pintype "bidirectional"))
      (node (ref "J3") (pin "1") (pinfunction "+_1") (pintype "bidirectional"))
      (node (ref "J3") (pin "4") (pinfunction "+_4") (pintype "bidirectional"))
      (node (ref "J7") (pin "1") (pinfunction "+_1") (pintype "bidirectional"))
      (node (ref "J7") (pin "4") (pinfunction "+_4") (pintype "bidirectional"))
      (node (ref "J8") (pin "1") (pinfunction "+_1") (pintype "bidirectional"))
      (node (ref "J8") (pin "4") (pinfunction "+_4") (pintype "bidirectional"))
      (node (ref "R8") (pin "1") (pinfunction "1_1") (pintype "passive"))
    )
    (net (code "20") (name "LCD_RX") (class "Default")
      (node (ref "L1") (pin "RXI") (pinfunction "RX_RXI") (pintype "bidirectional"))
      (node (ref "U4") (pin "32") (pinfunction "PD7(T0)_32") (pintype "bidirectional"))
    )
    (net (code "21") (name "LCD_TX") (class "Default")
      (node (ref "L1") (pin "TX0") (pinfunction "TX_TX0") (pintype "bidirectional"))
      (node (ref "U4") (pin "31") (pinfunction "PD6(T1)_31") (pintype "bidirectional"))
    )
    (net (code "22") (name "MISO") (class "Default")
      (node (ref "J4") (pin "1") (pinfunction "1_1") (pintype "passive"))
      (node (ref "U4") (pin "39") (pinfunction "PB3(MISO/PDO/PCINT3)_39") (pintype "bidirectional"))
    )
    (net (code "23") (name "MOSI") (class "Default")
      (node (ref "J4") (pin "4") (pinfunction "4_4") (pintype "passive"))
      (node (ref "U4") (pin "38") (pinfunction "PB2(MOSI/PDI/PCINT2)_38") (pintype "bidirectional"))
    )
    (net (code "24") (name "Net-(A1-SIGNAL)") (class "Default")
      (node (ref "A1") (pin "FEED") (pinfunction "SIGNAL_FEED") (pintype "bidirectional"))
      (node (ref "B2") (pin "1") (pinfunction "IN_1") (pintype "bidirectional"))
      (node (ref "C2") (pin "1") (pinfunction "1_1") (pintype "passive"))
    )
    (net (code "25") (name "Net-(B2-GND-Pad2)") (class "Default")
      (node (ref "B2") (pin "2") (pinfunction "GND_2") (pintype "bidirectional"))
      (node (ref "C3") (pin "2") (pinfunction "2_2") (pintype "passive"))
    )
    (net (code "26") (name "Net-(B2-OUT1)") (class "Default")
      (node (ref "B2") (pin "4") (pinfunction "OUT1_4") (pintype "bidirectional"))
      (node (ref "U4") (pin "8") (pinfunction "RFP_8") (pintype "bidirectional"))
    )
    (net (code "27") (name "Net-(B2-OUT2)") (class "Default")
      (node (ref "B2") (pin "3") (pinfunction "OUT2_3") (pintype "bidirectional"))
      (node (ref "U4") (pin "9") (pinfunction "RFN_9") (pintype "bidirectional"))
    )
    (net (code "28") (name "Net-(C11-Pad1)") (class "Default")
      (node (ref "C11") (pin "1") (pinfunction "1_1") (pintype "passive"))
      (node (ref "U4") (pin "21") (pinfunction "DVDD_21") (pintype "bidirectional"))
      (node (ref "U4") (pin "22") (pinfunction "DVDD_22") (pintype "bidirectional"))
    )
    (net (code "29") (name "Net-(R4A-1)") (class "Default")
      (node (ref "D1") (pin "A1") (pinfunction "A1_A1") (pintype "passive"))
      (node (ref "R4") (pin "4") (pinfunction "1_4") (pintype "passive"))
    )
    (net (code "30") (name "Net-(R4A-2)") (class "Default")
      (node (ref "R4") (pin "5") (pinfunction "2_5") (pintype "passive"))
      (node (ref "R4") (pin "6") (pinfunction "2_6") (pintype "passive"))
      (node (ref "U2") (pin "1") (pinfunction "STAT_1") (pintype "output"))
    )
    (net (code "31") (name "Net-(R4B-1)") (class "Default")
      (node (ref "D1") (pin "C2") (pinfunction "C2_C2") (pintype "passive"))
      (node (ref "R4") (pin "3") (pinfunction "1_3") (pintype "passive"))
    )
    (net (code "32") (name "Net-(R4C-2)") (class "Default")
      (node (ref "D4") (pin "C1") (pinfunction "C1_C1") (pintype "passive"))
      (node (ref "R4") (pin "7") (pinfunction "2_7") (pintype "passive"))
    )
    (net (code "33") (name "Net-(R4D-2)") (class "Default")
      (node (ref "D4") (pin "C2") (pinfunction "C2_C2") (pintype "passive"))
      (node (ref "R4") (pin "8") (pinfunction "2_8") (pintype "passive"))
    )
    (net (code "34") (name "Net-(R5A-1)") (class "Default")
      (node (ref "D5") (pin "A2") (pinfunction "A2_A2") (pintype "passive"))
      (node (ref "R5") (pin "4") (pinfunction "1_4") (pintype "passive"))
    )
    (net (code "35") (name "Net-(R5B-1)") (class "Default")
      (node (ref "D5") (pin "A1") (pinfunction "A1_A1") (pintype "passive"))
      (node (ref "R5") (pin "3") (pinfunction "1_3") (pintype "passive"))
    )
    (net (code "36") (name "Net-(R5C-2)") (class "Default")
      (node (ref "D6") (pin "C1") (pinfunction "C1_C1") (pintype "passive"))
      (node (ref "R5") (pin "7") (pinfunction "2_7") (pintype "passive"))
    )
    (net (code "37") (name "Net-(R5D-2)") (class "Default")
      (node (ref "D6") (pin "C2") (pinfunction "C2_C2") (pintype "passive"))
      (node (ref "R5") (pin "8") (pinfunction "2_8") (pintype "passive"))
    )
    (net (code "38") (name "Net-(S2-C)") (class "Default")
      (node (ref "S2") (pin "2") (pinfunction "C_2") (pintype "bidirectional"))
      (node (ref "U5") (pin "12") (pinfunction "2S_12") (pintype "bidirectional"))
      (node (ref "U5") (pin "4") (pinfunction "1S_4") (pintype "bidirectional"))
    )
    (net (code "39") (name "Net-(U2-PROG)") (class "Default")
      (node (ref "R7") (pin "1") (pinfunction "1_1") (pintype "passive"))
      (node (ref "U2") (pin "5") (pinfunction "PROG_5") (pintype "input"))
    )
    (net (code "40") (name "Net-(U2-VBAT)") (class "Default")
      (node (ref "B3") (pin "P") (pinfunction "P_P") (pintype "bidirectional"))
      (node (ref "C6") (pin "1") (pinfunction "1_1") (pintype "passive"))
      (node (ref "D3") (pin "A") (pinfunction "A_A") (pintype "passive"))
      (node (ref "U2") (pin "3") (pinfunction "VBAT_3") (pintype "power_in"))
      (node (ref "V30") (pin "P1") (pinfunction "N_P1") (pintype "bidirectional"))
      (node (ref "V31") (pin "P1") (pinfunction "N_P1") (pintype "bidirectional"))
      (node (ref "V32") (pin "P1") (pinfunction "N_P1") (pintype "bidirectional"))
      (node (ref "V33") (pin "P1") (pinfunction "N_P1") (pintype "bidirectional"))
      (node (ref "V34") (pin "P1") (pinfunction "N_P1") (pintype "bidirectional"))
      (node (ref "V36") (pin "P1") (pinfunction "N_P1") (pintype "bidirectional"))
      (node (ref "V6") (pin "P1") (pinfunction "N_P1") (pintype "bidirectional"))
    )
    (net (code "41") (name "Net-(U4-AVDD)") (class "Default")
      (node (ref "C13") (pin "1") (pinfunction "1_1") (pintype "passive"))
      (node (ref "U4") (pin "60") (pinfunction "AVDD_60") (pintype "bidirectional"))
    )
    (net (code "42") (name "Net-(U4-PG0(DIG3))") (class "Default")
      (node (ref "D6") (pin "A2") (pinfunction "A2_A2") (pintype "passive"))
      (node (ref "U4") (pin "14") (pinfunction "PG0(DIG3)_14") (pintype "bidirectional"))
    )
    (net (code "43") (name "Net-(U4-PG1(DIG1))") (class "Default")
      (node (ref "D6") (pin "A1") (pinfunction "A1_A1") (pintype "passive"))
      (node (ref "U4") (pin "15") (pinfunction "PG1(DIG1)_15") (pintype "bidirectional"))
    )
    (net (code "44") (name "Net-(U4-XTAL1)") (class "Default")
      (node (ref "C14") (pin "1") (pinfunction "1_1") (pintype "passive"))
      (node (ref "U4") (pin "57") (pinfunction "XTAL1_57") (pintype "bidirectional"))
      (node (ref "Y1") (pin "3") (pinfunction "2_3") (pintype "passive"))
    )
    (net (code "45") (name "Net-(U4-XTAL2)") (class "Default")
      (node (ref "C15") (pin "1") (pinfunction "1_1") (pintype "passive"))
      (node (ref "U4") (pin "56") (pinfunction "XTAL2_56") (pintype "bidirectional"))
      (node (ref "Y1") (pin "1") (pinfunction "1_1") (pintype "passive"))
    )
    (net (code "46") (name "PITCH") (class "Default")
      (node (ref "J3") (pin "V") (pinfunction "V_V") (pintype "bidirectional"))
      (node (ref "J8") (pin "V") (pinfunction "V_V") (pintype "bidirectional"))
      (node (ref "U4") (pin "2") (pinfunction "PF3(ADC3/DIG4)_2") (pintype "bidirectional"))
    )
    (net (code "47") (name "RESET") (class "Default")
      (node (ref "B1") (pin "1") (pinfunction "1_1") (pintype "passive"))
      (node (ref "B1") (pin "2") (pinfunction "1_2") (pintype "passive"))
      (node (ref "C1") (pin "1") (pinfunction "1_1") (pintype "passive"))
      (node (ref "J4") (pin "5") (pinfunction "5_5") (pintype "passive"))
      (node (ref "R2") (pin "1") (pinfunction "1_1") (pintype "passive"))
      (node (ref "U4") (pin "12") (pinfunction "RSTN_12") (pintype "bidirectional"))
    )
    (net (code "48") (name "RF") (class "Default")
      (node (ref "D4") (pin "A1") (pinfunction "A1_A1") (pintype "passive"))
      (node (ref "U4") (pin "16") (pinfunction "PG2(AMR)_16") (pintype "bidirectional"))
    )
    (net (code "49") (name "ROLL") (class "Default")
      (node (ref "J3") (pin "H") (pinfunction "H_H") (pintype "bidirectional"))
      (node (ref "J8") (pin "H") (pinfunction "H_H") (pintype "bidirectional"))
      (node (ref "U4") (pin "1") (pinfunction "PF2(ADC2/DIG2)_1") (pintype "bidirectional"))
    )
    (net (code "50") (name "RXI") (class "Default")
      (node (ref "U3") (pin "5") (pinfunction "RXD_5") (pintype "input"))
      (node (ref "U5") (pin "10") (pinfunction "3Z_10") (pintype "bidirectional"))
    )
    (net (code "51") (name "RXI-0") (class "Default")
      (node (ref "U4") (pin "47") (pinfunction "PE1(TXD0)_47") (pintype "bidirectional"))
      (node (ref "U5") (pin "11") (pinfunction "3Y0_11") (pintype "bidirectional"))
    )
    (net (code "52") (name "RXI-1") (class "Default")
      (node (ref "JP1") (pin "2") (pinfunction "2_2") (pintype "passive"))
      (node (ref "U5") (pin "9") (pinfunction "3Y1_9") (pintype "bidirectional"))
    )
    (net (code "53") (name "RXLED") (class "Default")
      (node (ref "D5") (pin "C2") (pinfunction "C2_C2") (pintype "passive"))
      (node (ref "U3") (pin "22") (pinfunction "RXLED_22") (pintype "input"))
    )
    (net (code "54") (name "SCK") (class "Default")
      (node (ref "J4") (pin "3") (pinfunction "3_3") (pintype "passive"))
      (node (ref "U4") (pin "37") (pinfunction "PB1(SCK/PCINT1)_37") (pintype "bidirectional"))
    )
    (net (code "55") (name "SHIELD") (class "Default")
      (node (ref "B12") (pin "P2") (pinfunction "P2_P2") (pintype "bidirectional"))
    )
    (net (code "56") (name "THROTTLE") (class "Default")
      (node (ref "J2") (pin "V") (pinfunction "V_V") (pintype "bidirectional"))
      (node (ref "J7") (pin "V") (pinfunction "V_V") (pintype "bidirectional"))
      (node (ref "U4") (pin "64") (pinfunction "PF1(ADC1)_64") (pintype "bidirectional"))
    )
    (net (code "57") (name "TXLED") (class "Default")
      (node (ref "D5") (pin "C1") (pinfunction "C1_C1") (pintype "passive"))
      (node (ref "U3") (pin "23") (pinfunction "TXLED_23") (pintype "input"))
    )
    (net (code "58") (name "TXO") (class "Default")
      (node (ref "U3") (pin "1") (pinfunction "TXD_1") (pintype "output"))
      (node (ref "U5") (pin "6") (pinfunction "2Z_6") (pintype "bidirectional"))
    )
    (net (code "59") (name "TXO-0") (class "Default")
      (node (ref "U4") (pin "46") (pinfunction "PE0(RXD0/PCINT8)_46") (pintype "bidirectional"))
      (node (ref "U5") (pin "7") (pinfunction "2Y0_7") (pintype "bidirectional"))
    )
    (net (code "60") (name "TXO-1") (class "Default")
      (node (ref "JP1") (pin "3") (pinfunction "3_3") (pintype "passive"))
      (node (ref "U5") (pin "5") (pinfunction "2Y1_5") (pintype "bidirectional"))
    )
    (net (code "61") (name "USB_D_N") (class "Default")
      (node (ref "J1") (pin "2") (pinfunction "2-D-_2") (pintype "bidirectional"))
      (node (ref "U3") (pin "16") (pinfunction "USBDM_16") (pintype "bidirectional"))
    )
    (net (code "62") (name "USB_D_P") (class "Default")
      (node (ref "J1") (pin "3") (pinfunction "3-D+_3") (pintype "bidirectional"))
      (node (ref "U3") (pin "15") (pinfunction "USBDP_15") (pintype "bidirectional"))
    )
    (net (code "63") (name "VBAT") (class "Default")
      (node (ref "D2") (pin "C") (pinfunction "C_C") (pintype "passive"))
      (node (ref "D3") (pin "C") (pinfunction "C_C") (pintype "passive"))
      (node (ref "P2") (pin "T") (pinfunction "T_T") (pintype "bidirectional"))
      (node (ref "S1") (pin "2") (pinfunction "C_2") (pintype "bidirectional"))
    )
    (net (code "64") (name "VBUS") (class "Default")
      (node (ref "C5") (pin "1") (pinfunction "1_1") (pintype "passive"))
      (node (ref "D1") (pin "A2") (pinfunction "A2_A2") (pintype "passive"))
      (node (ref "D2") (pin "A") (pinfunction "A_A") (pintype "passive"))
      (node (ref "J1") (pin "1") (pinfunction "1-VCC_1") (pintype "bidirectional"))
      (node (ref "P1") (pin "T") (pinfunction "T_T") (pintype "bidirectional"))
      (node (ref "U2") (pin "4") (pinfunction "VDD_4") (pintype "power_in"))
      (node (ref "V1") (pin "P1") (pinfunction "N_P1") (pintype "bidirectional"))
      (node (ref "V2") (pin "P1") (pinfunction "N_P1") (pintype "bidirectional"))
      (node (ref "V23") (pin "P1") (pinfunction "N_P1") (pintype "bidirectional"))
      (node (ref "V24") (pin "P1") (pinfunction "N_P1") (pintype "bidirectional"))
      (node (ref "V26") (pin "P1") (pinfunction "N_P1") (pintype "bidirectional"))
      (node (ref "V27") (pin "P1") (pinfunction "N_P1") (pintype "bidirectional"))
      (node (ref "V28") (pin "P1") (pinfunction "N_P1") (pintype "bidirectional"))
    )
    (net (code "65") (name "VREG_IN") (class "Default")
      (node (ref "C7") (pin "1") (pinfunction "1_1") (pintype "passive"))
      (node (ref "C8") (pin "1") (pinfunction "1_1") (pintype "passive"))
      (node (ref "L1") (pin "RAW") (pinfunction "VIN_RAW") (pintype "bidirectional"))
      (node (ref "S1") (pin "1") (pinfunction "ON_1") (pintype "bidirectional"))
      (node (ref "U3") (pin "20") (pinfunction "VCC_20") (pintype "power_in"))
    )
    (net (code "66") (name "YAW") (class "Default")
      (node (ref "J2") (pin "H") (pinfunction "H_H") (pintype "bidirectional"))
      (node (ref "J7") (pin "H") (pinfunction "H_H") (pintype "bidirectional"))
      (node (ref "U4") (pin "63") (pinfunction "PF0(ADC0)_63") (pintype "bidirectional"))
    )
    (net (code "67") (name "unconnected-(J1-4-ID-Pad4)") (class "Default")
      (node (ref "J1") (pin "4") (pinfunction "4-ID_4") (pintype "bidirectional"))
    )
    (net (code "68") (name "unconnected-(L1-PadSCK)") (class "Default")
      (node (ref "L1") (pin "SCK") (pinfunction "SCK_SCK") (pintype "bidirectional"))
    )
    (net (code "69") (name "unconnected-(L1-PadSDI)") (class "Default")
      (node (ref "L1") (pin "SDI") (pinfunction "SDI_SDI") (pintype "bidirectional"))
    )
    (net (code "70") (name "unconnected-(L1-PadSDO)") (class "Default")
      (node (ref "L1") (pin "SDO") (pinfunction "SDO_SDO") (pintype "bidirectional"))
    )
    (net (code "71") (name "unconnected-(L1-Pad{slash}CS)") (class "Default")
      (node (ref "L1") (pin "/CS") (pinfunction "/CS_/CS") (pintype "bidirectional"))
    )
    (net (code "72") (name "unconnected-(L1-SCL-PadCL)") (class "Default")
      (node (ref "L1") (pin "CL") (pinfunction "SCL_CL") (pintype "bidirectional"))
    )
    (net (code "73") (name "unconnected-(L1-SDA-PadDA)") (class "Default")
      (node (ref "L1") (pin "DA") (pinfunction "SDA_DA") (pintype "bidirectional"))
    )
    (net (code "74") (name "unconnected-(S1-OFF-Pad3)") (class "Default")
      (node (ref "S1") (pin "3") (pinfunction "OFF_3") (pintype "bidirectional"))
    )
    (net (code "75") (name "unconnected-(U3-DCD-Pad10)") (class "Default")
      (node (ref "U3") (pin "10") (pinfunction "DCD_10") (pintype "input"))
    )
    (net (code "76") (name "unconnected-(U3-DSR-Pad9)") (class "Default")
      (node (ref "U3") (pin "9") (pinfunction "DSR_9") (pintype "input"))
    )
    (net (code "77") (name "unconnected-(U3-OSCI-Pad27)") (class "Default")
      (node (ref "U3") (pin "27") (pinfunction "OSCI_27") (pintype "input"))
    )
    (net (code "78") (name "unconnected-(U3-OSCO-Pad28)") (class "Default")
      (node (ref "U3") (pin "28") (pinfunction "OSCO_28") (pintype "output"))
    )
    (net (code "79") (name "unconnected-(U3-PWREN-Pad14)") (class "Default")
      (node (ref "U3") (pin "14") (pinfunction "PWREN_14") (pintype "input"))
    )
    (net (code "80") (name "unconnected-(U3-RESET-Pad19)") (class "Default")
      (node (ref "U3") (pin "19") (pinfunction "RESET_19") (pintype "input"))
    )
    (net (code "81") (name "unconnected-(U3-RI-Pad6)") (class "Default")
      (node (ref "U3") (pin "6") (pinfunction "RI_6") (pintype "input"))
    )
    (net (code "82") (name "unconnected-(U3-RTS-Pad3)") (class "Default")
      (node (ref "U3") (pin "3") (pinfunction "RTS_3") (pintype "output"))
    )
    (net (code "83") (name "unconnected-(U3-SLEEP-Pad12)") (class "Default")
      (node (ref "U3") (pin "12") (pinfunction "SLEEP_12") (pintype "input"))
    )
    (net (code "84") (name "unconnected-(U3-TXDEN-Pad13)") (class "Default")
      (node (ref "U3") (pin "13") (pinfunction "TXDEN_13") (pintype "input"))
    )
    (net (code "85") (name "unconnected-(U4-AREF-Pad62)") (class "Default")
      (node (ref "U4") (pin "62") (pinfunction "AREF_62") (pintype "bidirectional"))
    )
    (net (code "86") (name "unconnected-(U4-PB0(SSN{slash}PCINT0)-Pad36)") (class "Default")
      (node (ref "U4") (pin "36") (pinfunction "PB0(SSN/PCINT0)_36") (pintype "bidirectional"))
    )
    (net (code "87") (name "unconnected-(U4-PB6(OC1B{slash}PCINT6)-Pad42)") (class "Default")
      (node (ref "U4") (pin "42") (pinfunction "PB6(OC1B/PCINT6)_42") (pintype "bidirectional"))
    )
    (net (code "88") (name "unconnected-(U4-PB7(OC0A{slash}OC1C{slash}PCINT7)-Pad43)") (class "Default")
      (node (ref "U4") (pin "43") (pinfunction "PB7(OC0A/OC1C/PCINT7)_43") (pintype "bidirectional"))
    )
    (net (code "89") (name "unconnected-(U4-PD4(ICP1)-Pad29)") (class "Default")
      (node (ref "U4") (pin "29") (pinfunction "PD4(ICP1)_29") (pintype "bidirectional"))
    )
    (net (code "90") (name "unconnected-(U4-PD5(XCK1)-Pad30)") (class "Default")
      (node (ref "U4") (pin "30") (pinfunction "PD5(XCK1)_30") (pintype "bidirectional"))
    )
    (net (code "91") (name "unconnected-(U4-PE2(XCK0{slash}AIN0)-Pad48)") (class "Default")
      (node (ref "U4") (pin "48") (pinfunction "PE2(XCK0/AIN0)_48") (pintype "bidirectional"))
    )
    (net (code "92") (name "unconnected-(U4-PE3(OC3A{slash}AIN1)-Pad49)") (class "Default")
      (node (ref "U4") (pin "49") (pinfunction "PE3(OC3A/AIN1)_49") (pintype "bidirectional"))
    )
    (net (code "93") (name "unconnected-(U4-PF4(ADC4{slash}TCK)-Pad3)") (class "Default")
      (node (ref "U4") (pin "3") (pinfunction "PF4(ADC4/TCK)_3") (pintype "bidirectional"))
    )
    (net (code "94") (name "unconnected-(U4-PF5(ADC5{slash}TMS)-Pad4)") (class "Default")
      (node (ref "U4") (pin "4") (pinfunction "PF5(ADC5/TMS)_4") (pintype "bidirectional"))
    )
    (net (code "95") (name "unconnected-(U4-PF6(ADC6{slash}TDO)-Pad5)") (class "Default")
      (node (ref "U4") (pin "5") (pinfunction "PF6(ADC6/TDO)_5") (pintype "bidirectional"))
    )
    (net (code "96") (name "unconnected-(U4-PF7(ADC7{slash}TDI)-Pad6)") (class "Default")
      (node (ref "U4") (pin "6") (pinfunction "PF7(ADC7/TDI)_6") (pintype "bidirectional"))
    )
    (net (code "97") (name "unconnected-(U4-PG3(TOSC2)-Pad17)") (class "Default")
      (node (ref "U4") (pin "17") (pinfunction "PG3(TOSC2)_17") (pintype "bidirectional"))
    )
    (net (code "98") (name "unconnected-(U4-PG4(TOSC1)-Pad18)") (class "Default")
      (node (ref "U4") (pin "18") (pinfunction "PG4(TOSC1)_18") (pintype "bidirectional"))
    )
    (net (code "99") (name "unconnected-(U4-PG5(OC0B)-Pad19)") (class "Default")
      (node (ref "U4") (pin "19") (pinfunction "PG5(OC0B)_19") (pintype "bidirectional"))
    )
    (net (code "100") (name "unconnected-(U4-RSTON-Pad13)") (class "Default")
      (node (ref "U4") (pin "13") (pinfunction "RSTON_13") (pintype "bidirectional"))
    )
  )
)
